# DW1000.net
KiCad netlist of a schematic drawn in Altium Designer
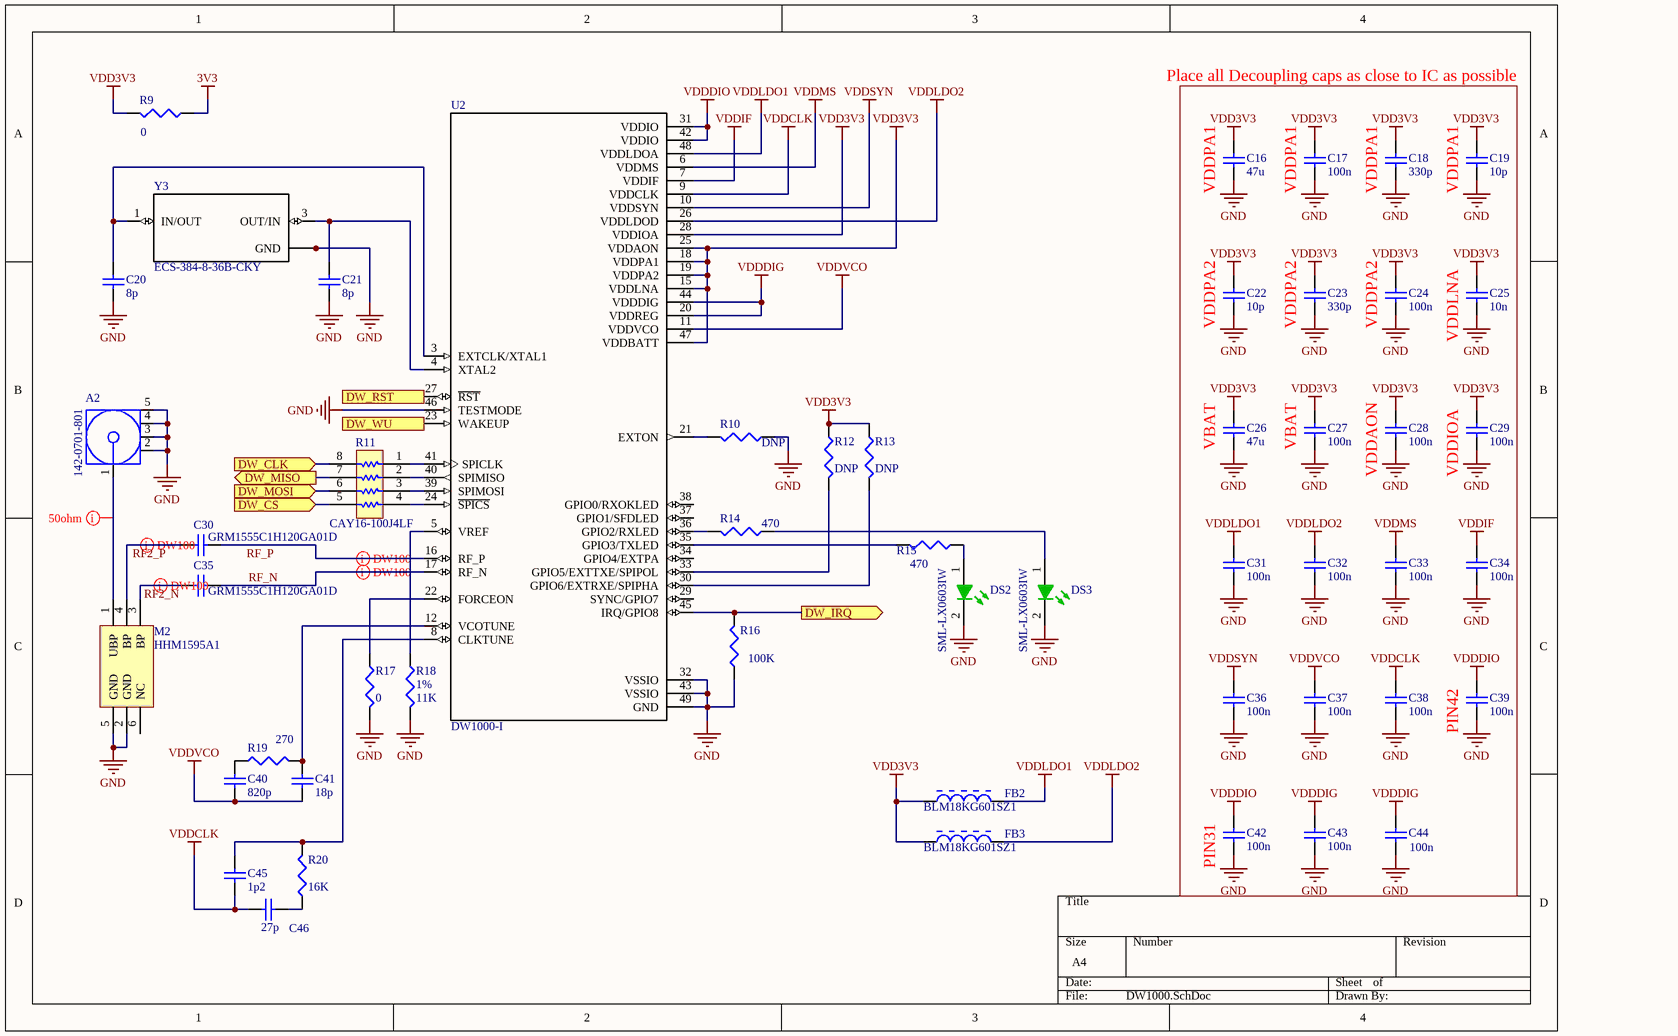
[diagram p0: DW1000.SchDoc]

(export (version "E")
  (design (tool "Eeschema 10.0.6"))
  (components
    (comp (ref "A2")
      (value "142-0701-801")
      (footprint "CINC-142-0701-801_V")
      (description "SMA End Launch Jack Receptacle, 50 Ohm, 0 to 18 GHz, -65 to 165 degC, 5-Pin SMD, RoHS, Bulk")
      (fields (field (name "MANUFACTURER") "EmersonConnectivitySolutions"))
      (libsource (lib "Altium Content Vault") (part "CN-S-4F-RF5"))
    )
    (comp (ref "C16")
      (value "47u")
      (footprint "CAPC1608X90X35NL10T15")
      (fields (field (name "PART NUMBER") "GRM188R71H102KA01D") (field (name "MANUFACTURER") "Murata"))
      (libsource (lib "Altium Content Vault") (part "CAP"))
    )
    (comp (ref "C17")
      (value "100n")
      (footprint "CAPC1608X90X35NL10T15")
      (fields (field (name "PART NUMBER") "GRM188R71H102KA01D") (field (name "MANUFACTURER") "Murata"))
      (libsource (lib "Altium Content Vault") (part "CAP"))
    )
    (comp (ref "C18")
      (value "330p")
      (footprint "CAPC1608X90X35NL10T15")
      (fields (field (name "PART NUMBER") "GRM188R71H102KA01D") (field (name "MANUFACTURER") "Murata"))
      (libsource (lib "Altium Content Vault") (part "CAP"))
    )
    (comp (ref "C19")
      (value "10p")
      (footprint "CAPC1608X90X35NL10T15")
      (fields (field (name "PART NUMBER") "GRM188R71H102KA01D") (field (name "MANUFACTURER") "Murata"))
      (libsource (lib "Altium Content Vault") (part "CAP"))
    )
    (comp (ref "C20")
      (value "8p")
      (footprint "CAPC1608X90X35NL10T15")
      (fields (field (name "PART NUMBER") "GRM188R71H102KA01D") (field (name "MANUFACTURER") "Murata"))
      (libsource (lib "Altium Content Vault") (part "CAP"))
    )
    (comp (ref "C21")
      (value "8p")
      (footprint "CAPC1608X90X35NL10T15")
      (fields (field (name "PART NUMBER") "GRM188R71H102KA01D") (field (name "MANUFACTURER") "Murata"))
      (libsource (lib "Altium Content Vault") (part "CAP"))
    )
    (comp (ref "C22")
      (value "10p")
      (footprint "CAPC1608X90X35NL10T15")
      (fields (field (name "PART NUMBER") "GRM188R71H102KA01D") (field (name "MANUFACTURER") "Murata"))
      (libsource (lib "Altium Content Vault") (part "CAP"))
    )
    (comp (ref "C23")
      (value "330p")
      (footprint "CAPC1608X90X35NL10T15")
      (fields (field (name "PART NUMBER") "GRM188R71H102KA01D") (field (name "MANUFACTURER") "Murata"))
      (libsource (lib "Altium Content Vault") (part "CAP"))
    )
    (comp (ref "C24")
      (value "100n")
      (footprint "CAPC1608X90X35NL10T15")
      (fields (field (name "PART NUMBER") "GRM188R71H102KA01D") (field (name "MANUFACTURER") "Murata"))
      (libsource (lib "Altium Content Vault") (part "CAP"))
    )
    (comp (ref "C25")
      (value "10n")
      (footprint "CAPC1608X90X35NL10T15")
      (fields (field (name "PART NUMBER") "GRM188R71H102KA01D") (field (name "MANUFACTURER") "Murata"))
      (libsource (lib "Altium Content Vault") (part "CAP"))
    )
    (comp (ref "C26")
      (value "47u")
      (footprint "CAPC1608X90X35NL10T15")
      (fields (field (name "PART NUMBER") "GRM188R71H102KA01D") (field (name "MANUFACTURER") "Murata"))
      (libsource (lib "Altium Content Vault") (part "CAP"))
    )
    (comp (ref "C27")
      (value "100n")
      (footprint "CAPC1608X90X35NL10T15")
      (fields (field (name "PART NUMBER") "GRM188R71H102KA01D") (field (name "MANUFACTURER") "Murata"))
      (libsource (lib "Altium Content Vault") (part "CAP"))
    )
    (comp (ref "C28")
      (value "100n")
      (footprint "CAPC1608X90X35NL10T15")
      (fields (field (name "PART NUMBER") "GRM188R71H102KA01D") (field (name "MANUFACTURER") "Murata"))
      (libsource (lib "Altium Content Vault") (part "CAP"))
    )
    (comp (ref "C29")
      (value "100n")
      (footprint "CAPC1608X90X35NL10T15")
      (fields (field (name "PART NUMBER") "GRM188R71H102KA01D") (field (name "MANUFACTURER") "Murata"))
      (libsource (lib "Altium Content Vault") (part "CAP"))
    )
    (comp (ref "C30")
      (value "GRM1555C1H120GA01D")
      (footprint "CAPC1005X55X25ML05T10")
      (fields (field (name "MANUFACTURER") "Murata"))
      (libsource (lib "Altium Content Vault") (part "CAP"))
    )
    (comp (ref "C31")
      (value "100n")
      (footprint "CAPC1608X90X35NL10T15")
      (fields (field (name "PART NUMBER") "GRM188R71H102KA01D") (field (name "MANUFACTURER") "Murata"))
      (libsource (lib "Altium Content Vault") (part "CAP"))
    )
    (comp (ref "C32")
      (value "100n")
      (footprint "CAPC1608X90X35NL10T15")
      (fields (field (name "PART NUMBER") "GRM188R71H102KA01D") (field (name "MANUFACTURER") "Murata"))
      (libsource (lib "Altium Content Vault") (part "CAP"))
    )
    (comp (ref "C33")
      (value "100n")
      (footprint "CAPC1608X90X35NL10T15")
      (fields (field (name "PART NUMBER") "GRM188R71H102KA01D") (field (name "MANUFACTURER") "Murata"))
      (libsource (lib "Altium Content Vault") (part "CAP"))
    )
    (comp (ref "C34")
      (value "100n")
      (footprint "CAPC1608X90X35NL10T15")
      (fields (field (name "PART NUMBER") "GRM188R71H102KA01D") (field (name "MANUFACTURER") "Murata"))
      (libsource (lib "Altium Content Vault") (part "CAP"))
    )
    (comp (ref "C35")
      (value "GRM1555C1H120GA01D")
      (footprint "CAPC1005X55X25ML05T10")
      (fields (field (name "MANUFACTURER") "Murata"))
      (libsource (lib "Altium Content Vault") (part "CAP"))
    )
    (comp (ref "C36")
      (value "100n")
      (footprint "CAPC1608X90X35NL10T15")
      (fields (field (name "PART NUMBER") "GRM188R71H102KA01D") (field (name "MANUFACTURER") "Murata"))
      (libsource (lib "Altium Content Vault") (part "CAP"))
    )
    (comp (ref "C37")
      (value "100n")
      (footprint "CAPC1608X90X35NL10T15")
      (fields (field (name "PART NUMBER") "GRM188R71H102KA01D") (field (name "MANUFACTURER") "Murata"))
      (libsource (lib "Altium Content Vault") (part "CAP"))
    )
    (comp (ref "C38")
      (value "100n")
      (footprint "CAPC1608X90X35NL10T15")
      (fields (field (name "PART NUMBER") "GRM188R71H102KA01D") (field (name "MANUFACTURER") "Murata"))
      (libsource (lib "Altium Content Vault") (part "CAP"))
    )
    (comp (ref "C39")
      (value "100n")
      (footprint "CAPC1608X90X35NL10T15")
      (fields (field (name "PART NUMBER") "GRM188R71H102KA01D") (field (name "MANUFACTURER") "Murata"))
      (libsource (lib "Altium Content Vault") (part "CAP"))
    )
    (comp (ref "C40")
      (value "820p")
      (footprint "CAPC1608X90X35NL10T15")
      (fields (field (name "PART NUMBER") "GRM188R71H102KA01D") (field (name "MANUFACTURER") "Murata"))
      (libsource (lib "Altium Content Vault") (part "CAP"))
    )
    (comp (ref "C41")
      (value "18p")
      (footprint "CAPC1608X90X35NL10T15")
      (fields (field (name "PART NUMBER") "GRM188R71H102KA01D") (field (name "MANUFACTURER") "Murata"))
      (libsource (lib "Altium Content Vault") (part "CAP"))
    )
    (comp (ref "C42")
      (value "100n")
      (footprint "CAPC1608X90X35NL10T15")
      (fields (field (name "PART NUMBER") "GRM188R71H102KA01D") (field (name "MANUFACTURER") "Murata"))
      (libsource (lib "Altium Content Vault") (part "CAP"))
    )
    (comp (ref "C43")
      (value "100n")
      (footprint "CAPC1608X90X35NL10T15")
      (fields (field (name "PART NUMBER") "GRM188R71H102KA01D") (field (name "MANUFACTURER") "Murata"))
      (libsource (lib "Altium Content Vault") (part "CAP"))
    )
    (comp (ref "C44")
      (value "100n")
      (footprint "CAPC1608X90X35NL10T15")
      (fields (field (name "PART NUMBER") "GRM188R71H102KA01D") (field (name "MANUFACTURER") "Murata"))
      (libsource (lib "Altium Content Vault") (part "CAP"))
    )
    (comp (ref "C45")
      (value "1p2")
      (footprint "CAPC1608X90X35NL10T15")
      (fields (field (name "PART NUMBER") "GRM188R71H102KA01D") (field (name "MANUFACTURER") "Murata"))
      (libsource (lib "Altium Content Vault") (part "CAP"))
    )
    (comp (ref "C46")
      (value "27p")
      (footprint "CAPC1608X90X35NL10T15")
      (fields (field (name "PART NUMBER") "GRM188R71H102KA01D") (field (name "MANUFACTURER") "Murata"))
      (libsource (lib "Altium Content Vault") (part "CAP"))
    )
    (comp (ref "DS2")
      (value "SML-LX0603IW")
      (footprint "KING-0603LED_GREEN_V")
      (description "LED, SMT, 0603(1608), 1.1mm thickness, Green")
      (fields (field (name "MANUFACTURER") "Kingbright") (field (name "PARTNUMBER") "KP-1608MGC"))
      (libsource (lib "Altium Content Vault") (part "KING-LED-GREEN-A1K2-2"))
    )
    (comp (ref "DS3")
      (value "SML-LX0603IW")
      (footprint "KING-0603LED_GREEN_V")
      (description "LED, SMT, 0603(1608), 1.1mm thickness, Green")
      (fields (field (name "MANUFACTURER") "Kingbright") (field (name "PARTNUMBER") "KP-1608MGC"))
      (libsource (lib "Altium Content Vault") (part "KING-LED-GREEN-A1K2-2"))
    )
    (comp (ref "FB2")
      (value "BLM18KG601SZ1")
      (footprint "MURA-BLM18SG-B25-CHIP-2_V1")
      (fields (field (name "MANUFACTURER") "Murata") (field (name "PARTNUMBER") "BLM18SG221TN1D"))
      (libsource (lib "Altium Content Vault") (part "MURA-FB-2"))
    )
    (comp (ref "FB3")
      (value "BLM18KG601SZ1")
      (footprint "MURA-BLM18SG-B25-CHIP-2_V1")
      (fields (field (name "MANUFACTURER") "Murata") (field (name "PARTNUMBER") "BLM18SG221TN1D"))
      (libsource (lib "Altium Content Vault") (part "MURA-FB-2"))
    )
    (comp (ref "M2")
      (value "HHM1595A1")
      (footprint "TDK-HHM1595A1_V")
      (description "Multilayer Balun, 3000 to 8000 MHz, -40 to 85 degC, 6-Pin SMD, RoHS, Tape and Reel")
      (fields (field (name "MANUFACTURER") "TDK"))
      (libsource (lib "Altium Content Vault") (part "TDK-HHM1595A1-6"))
    )
    (comp (ref "R9")
      (value "0")
      (footprint "J1-0603")
      (description "Resistor")
      (fields (field (name "PUBLISHER") "Altium Limited"))
      (libsource (lib "Miscellaneous Devices") (part "Res3"))
    )
    (comp (ref "R10")
      (value "DNP")
      (footprint "J1-0603")
      (description "Resistor")
      (fields (field (name "PUBLISHER") "Altium Limited"))
      (libsource (lib "Miscellaneous Devices") (part "Res3"))
    )
    (comp (ref "R11")
      (value "CAY16-100J4LF")
      (footprint "BOUR-CAY16-J4_V")
      (description "Chip Resistor Array, 1 KOhm, +/- 5%, 62.5 mW, -55 to 125 degC, 8-Pin SMD, RoHS, Tape and Reel")
      (fields (field (name "TOLERANCE") "1%"))
      (libsource (lib "Altium Content Vault") (part "RES-P-8"))
    )
    (comp (ref "R12")
      (value "DNP")
      (footprint "J1-0603")
      (description "Resistor")
      (fields (field (name "PUBLISHER") "Altium Limited"))
      (libsource (lib "Miscellaneous Devices") (part "Res3"))
    )
    (comp (ref "R13")
      (value "DNP")
      (footprint "J1-0603")
      (description "Resistor")
      (fields (field (name "PUBLISHER") "Altium Limited"))
      (libsource (lib "Miscellaneous Devices") (part "Res3"))
    )
    (comp (ref "R14")
      (value "470")
      (footprint "J1-0603")
      (description "Resistor")
      (fields (field (name "PUBLISHER") "Altium Limited"))
      (libsource (lib "Miscellaneous Devices") (part "Res3"))
    )
    (comp (ref "R15")
      (value "470")
      (footprint "J1-0603")
      (description "Resistor")
      (fields (field (name "PUBLISHER") "Altium Limited"))
      (libsource (lib "Miscellaneous Devices") (part "Res3"))
    )
    (comp (ref "R16")
      (value "100K")
      (footprint "J1-0603")
      (description "Resistor")
      (fields (field (name "PUBLISHER") "Altium Limited"))
      (libsource (lib "Miscellaneous Devices") (part "Res3"))
    )
    (comp (ref "R17")
      (value "0")
      (footprint "J1-0603")
      (description "Resistor")
      (fields (field (name "PUBLISHER") "Altium Limited"))
      (libsource (lib "Miscellaneous Devices") (part "Res3"))
    )
    (comp (ref "R18")
      (value "1%")
      (footprint "J1-0603")
      (description "Resistor")
      (fields (field (name "ALTIUM_VALUE") "11K") (field (name "PUBLISHER") "Altium Limited"))
      (libsource (lib "Miscellaneous Devices") (part "Res3"))
    )
    (comp (ref "R19")
      (value "270")
      (footprint "J1-0603")
      (description "Resistor")
      (fields (field (name "PUBLISHER") "Altium Limited"))
      (libsource (lib "Miscellaneous Devices") (part "Res3"))
    )
    (comp (ref "R20")
      (value "16K")
      (footprint "J1-0603")
      (description "Resistor")
      (fields (field (name "PUBLISHER") "Altium Limited"))
      (libsource (lib "Miscellaneous Devices") (part "Res3"))
    )
    (comp (ref "U2")
      (value "DW1000-I")
      (footprint "*QFN40P600X600X90-49N")
      (description "Ic Rf Txrx 802.15.4 48-Qfn")
      (fields (field (name "MF") "Decawave Limited"))
      (libsource (lib "DW1000-I") (part "DW1000-I"))
    )
    (comp (ref "Y3")
      (value "ECS-384-8-36B-CKY")
      (footprint "*XTAL_ECS-240-8-36-CKM-TR")
      (fields (field (name "MF") "ECS Inc.") (field (name "MP") "ECS-240-8-36-CKM-TR"))
      (libsource (lib "ECS-240-8-36-CKM-TR") (part "ECS-240-8-36-CKM-TR"))
    )
  )
  (nets
    (net (code "1") (name "/DW_CLK") (class "Default")
      (node (ref "R11") (pin "8") (pinfunction "8_8") (pintype "passive"))
    )
    (net (code "2") (name "/DW_CS") (class "Default")
      (node (ref "R11") (pin "5") (pinfunction "5_5") (pintype "passive"))
    )
    (net (code "3") (name "/DW_IRQ") (class "Default")
      (node (ref "R16") (pin "2") (pinfunction "2_2") (pintype "passive"))
      (node (ref "U2") (pin "45") (pinfunction "IRQ/GPIO8_45") (pintype "bidirectional"))
    )
    (net (code "4") (name "/DW_MISO") (class "Default")
      (node (ref "R11") (pin "7") (pinfunction "7_7") (pintype "passive"))
    )
    (net (code "5") (name "/DW_MOSI") (class "Default")
      (node (ref "R11") (pin "6") (pinfunction "6_6") (pintype "passive"))
    )
    (net (code "6") (name "/DW_RST") (class "Default")
      (node (ref "U2") (pin "27") (pinfunction "~{RST}_27") (pintype "bidirectional"))
    )
    (net (code "7") (name "/DW_WU") (class "Default")
      (node (ref "U2") (pin "23") (pinfunction "WAKEUP_23") (pintype "input"))
    )
    (net (code "8") (name "/RF2_N") (class "Default")
      (node (ref "C35") (pin "1") (pinfunction "1_1") (pintype "passive"))
      (node (ref "M2") (pin "3") (pinfunction "BP_3") (pintype "passive"))
    )
    (net (code "9") (name "/RF2_P") (class "Default")
      (node (ref "C30") (pin "1") (pinfunction "1_1") (pintype "passive"))
      (node (ref "M2") (pin "4") (pinfunction "BP_4") (pintype "passive"))
    )
    (net (code "10") (name "/RF_N") (class "Default")
      (node (ref "C35") (pin "2") (pinfunction "2_2") (pintype "passive"))
      (node (ref "U2") (pin "17") (pinfunction "RF_N_17") (pintype "bidirectional"))
    )
    (net (code "11") (name "/RF_P") (class "Default")
      (node (ref "C30") (pin "2") (pinfunction "2_2") (pintype "passive"))
      (node (ref "U2") (pin "16") (pinfunction "RF_P_16") (pintype "bidirectional"))
    )
    (net (code "12") (name "3V3") (class "Default")
      (node (ref "R9") (pin "1") (pinfunction "1_1") (pintype "passive"))
    )
    (net (code "13") (name "GND") (class "Default")
      (node (ref "A2") (pin "2") (pinfunction "2_2") (pintype "passive"))
      (node (ref "A2") (pin "3") (pinfunction "3_3") (pintype "passive"))
      (node (ref "A2") (pin "4") (pinfunction "4_4") (pintype "passive"))
      (node (ref "A2") (pin "5") (pinfunction "5_5") (pintype "passive"))
      (node (ref "C16") (pin "1") (pinfunction "1_1") (pintype "passive"))
      (node (ref "C17") (pin "1") (pinfunction "1_1") (pintype "passive"))
      (node (ref "C18") (pin "1") (pinfunction "1_1") (pintype "passive"))
      (node (ref "C19") (pin "1") (pinfunction "1_1") (pintype "passive"))
      (node (ref "C20") (pin "1") (pinfunction "1_1") (pintype "passive"))
      (node (ref "C21") (pin "1") (pinfunction "1_1") (pintype "passive"))
      (node (ref "C22") (pin "1") (pinfunction "1_1") (pintype "passive"))
      (node (ref "C23") (pin "1") (pinfunction "1_1") (pintype "passive"))
      (node (ref "C24") (pin "1") (pinfunction "1_1") (pintype "passive"))
      (node (ref "C25") (pin "1") (pinfunction "1_1") (pintype "passive"))
      (node (ref "C26") (pin "1") (pinfunction "1_1") (pintype "passive"))
      (node (ref "C27") (pin "1") (pinfunction "1_1") (pintype "passive"))
      (node (ref "C28") (pin "1") (pinfunction "1_1") (pintype "passive"))
      (node (ref "C29") (pin "1") (pinfunction "1_1") (pintype "passive"))
      (node (ref "C31") (pin "1") (pinfunction "1_1") (pintype "passive"))
      (node (ref "C32") (pin "1") (pinfunction "1_1") (pintype "passive"))
      (node (ref "C33") (pin "1") (pinfunction "1_1") (pintype "passive"))
      (node (ref "C34") (pin "1") (pinfunction "1_1") (pintype "passive"))
      (node (ref "C36") (pin "1") (pinfunction "1_1") (pintype "passive"))
      (node (ref "C37") (pin "1") (pinfunction "1_1") (pintype "passive"))
      (node (ref "C38") (pin "1") (pinfunction "1_1") (pintype "passive"))
      (node (ref "C39") (pin "1") (pinfunction "1_1") (pintype "passive"))
      (node (ref "C42") (pin "1") (pinfunction "1_1") (pintype "passive"))
      (node (ref "C43") (pin "1") (pinfunction "1_1") (pintype "passive"))
      (node (ref "C44") (pin "1") (pinfunction "1_1") (pintype "passive"))
      (node (ref "DS2") (pin "2") (pinfunction "K_2") (pintype "passive"))
      (node (ref "DS3") (pin "2") (pinfunction "K_2") (pintype "passive"))
      (node (ref "M2") (pin "2") (pinfunction "GND_2") (pintype "power_in"))
      (node (ref "M2") (pin "5") (pinfunction "GND_5") (pintype "power_in"))
      (node (ref "R10") (pin "1") (pinfunction "1_1") (pintype "passive"))
      (node (ref "R16") (pin "1") (pinfunction "1_1") (pintype "passive"))
      (node (ref "R17") (pin "2") (pinfunction "2_2") (pintype "passive"))
      (node (ref "R18") (pin "2") (pinfunction "2_2") (pintype "passive"))
      (node (ref "U2") (pin "32") (pinfunction "VSSIO_32") (pintype "power_in"))
      (node (ref "U2") (pin "43") (pinfunction "VSSIO_43") (pintype "power_in"))
      (node (ref "U2") (pin "46") (pinfunction "TESTMODE_46") (pintype "input"))
      (node (ref "U2") (pin "49") (pinfunction "GND_49") (pintype "power_in"))
      (node (ref "Y3") (pin "2") (pinfunction "GND_2") (pintype "power_in"))
      (node (ref "Y3") (pin "4") (pinfunction "GND_4") (pintype "power_in"))
    )
    (net (code "14") (name "Net-(C40-Pad2)") (class "Default")
      (node (ref "C40") (pin "2") (pinfunction "2_2") (pintype "passive"))
      (node (ref "R19") (pin "1") (pinfunction "1_1") (pintype "passive"))
    )
    (net (code "15") (name "Net-(C46-Pad1)") (class "Default")
      (node (ref "C46") (pin "1") (pinfunction "1_1") (pintype "passive"))
      (node (ref "R20") (pin "1") (pinfunction "1_1") (pintype "passive"))
    )
    (net (code "16") (name "Net-(DS2-A)") (class "Default")
      (node (ref "DS2") (pin "1") (pinfunction "A_1") (pintype "passive"))
      (node (ref "R15") (pin "1") (pinfunction "1_1") (pintype "passive"))
    )
    (net (code "17") (name "Net-(DS3-A)") (class "Default")
      (node (ref "DS3") (pin "1") (pinfunction "A_1") (pintype "passive"))
      (node (ref "R14") (pin "1") (pinfunction "1_1") (pintype "passive"))
    )
    (net (code "18") (name "Net-(M2-UBP)") (class "Default")
      (node (ref "A2") (pin "1") (pinfunction "1_1") (pintype "passive"))
      (node (ref "M2") (pin "1") (pinfunction "UBP_1") (pintype "passive"))
    )
    (net (code "19") (name "Net-(U2-CLKTUNE)") (class "Default")
      (node (ref "C45") (pin "2") (pinfunction "2_2") (pintype "passive"))
      (node (ref "R20") (pin "2") (pinfunction "2_2") (pintype "passive"))
      (node (ref "U2") (pin "8") (pinfunction "CLKTUNE_8") (pintype "bidirectional"))
    )
    (net (code "20") (name "Net-(U2-EXTCLK{slash}XTAL1)") (class "Default")
      (node (ref "C20") (pin "2") (pinfunction "2_2") (pintype "passive"))
      (node (ref "U2") (pin "3") (pinfunction "EXTCLK/XTAL1_3") (pintype "input"))
      (node (ref "Y3") (pin "1") (pinfunction "IN/OUT_1") (pintype "bidirectional"))
    )
    (net (code "21") (name "Net-(U2-EXTON)") (class "Default")
      (node (ref "R10") (pin "2") (pinfunction "2_2") (pintype "passive"))
      (node (ref "U2") (pin "21") (pinfunction "EXTON_21") (pintype "output"))
    )
    (net (code "22") (name "Net-(U2-FORCEON)") (class "Default")
      (node (ref "R17") (pin "1") (pinfunction "1_1") (pintype "passive"))
      (node (ref "U2") (pin "22") (pinfunction "FORCEON_22") (pintype "bidirectional"))
    )
    (net (code "23") (name "Net-(U2-GPIO2{slash}RXLED)") (class "Default")
      (node (ref "R14") (pin "2") (pinfunction "2_2") (pintype "passive"))
      (node (ref "U2") (pin "36") (pinfunction "GPIO2/RXLED_36") (pintype "bidirectional"))
    )
    (net (code "24") (name "Net-(U2-GPIO3{slash}TXLED)") (class "Default")
      (node (ref "R15") (pin "2") (pinfunction "2_2") (pintype "passive"))
      (node (ref "U2") (pin "35") (pinfunction "GPIO3/TXLED_35") (pintype "bidirectional"))
    )
    (net (code "25") (name "Net-(U2-GPIO5{slash}EXTTXE{slash}SPIPOL)") (class "Default")
      (node (ref "R12") (pin "2") (pinfunction "2_2") (pintype "passive"))
      (node (ref "U2") (pin "33") (pinfunction "GPIO5/EXTTXE/SPIPOL_33") (pintype "bidirectional"))
    )
    (net (code "26") (name "Net-(U2-GPIO6{slash}EXTRXE{slash}SPIPHA)") (class "Default")
      (node (ref "R13") (pin "2") (pinfunction "2_2") (pintype "passive"))
      (node (ref "U2") (pin "30") (pinfunction "GPIO6/EXTRXE/SPIPHA_30") (pintype "bidirectional"))
    )
    (net (code "27") (name "Net-(U2-SPICLK)") (class "Default")
      (node (ref "R11") (pin "1") (pinfunction "1_1") (pintype "passive"))
      (node (ref "U2") (pin "41") (pinfunction "SPICLK_41") (pintype "input"))
    )
    (net (code "28") (name "Net-(U2-SPIMISO)") (class "Default")
      (node (ref "R11") (pin "2") (pinfunction "2_2") (pintype "passive"))
      (node (ref "U2") (pin "40") (pinfunction "SPIMISO_40") (pintype "output"))
    )
    (net (code "29") (name "Net-(U2-SPIMOSI)") (class "Default")
      (node (ref "R11") (pin "3") (pinfunction "3_3") (pintype "passive"))
      (node (ref "U2") (pin "39") (pinfunction "SPIMOSI_39") (pintype "input"))
    )
    (net (code "30") (name "Net-(U2-VCOTUNE)") (class "Default")
      (node (ref "C41") (pin "2") (pinfunction "2_2") (pintype "passive"))
      (node (ref "R19") (pin "2") (pinfunction "2_2") (pintype "passive"))
      (node (ref "U2") (pin "12") (pinfunction "VCOTUNE_12") (pintype "bidirectional"))
    )
    (net (code "31") (name "Net-(U2-VREF)") (class "Default")
      (node (ref "R18") (pin "1") (pinfunction "1_1") (pintype "passive"))
      (node (ref "U2") (pin "5") (pinfunction "VREF_5") (pintype "bidirectional"))
    )
    (net (code "32") (name "Net-(U2-XTAL2)") (class "Default")
      (node (ref "C21") (pin "2") (pinfunction "2_2") (pintype "passive"))
      (node (ref "U2") (pin "4") (pinfunction "XTAL2_4") (pintype "input"))
      (node (ref "Y3") (pin "3") (pinfunction "OUT/IN_3") (pintype "bidirectional"))
    )
    (net (code "33") (name "Net-(U2-~{SPICS})") (class "Default")
      (node (ref "R11") (pin "4") (pinfunction "4_4") (pintype "passive"))
      (node (ref "U2") (pin "24") (pinfunction "~{SPICS}_24") (pintype "input"))
    )
    (net (code "34") (name "VDD3V3") (class "Default")
      (node (ref "C16") (pin "2") (pinfunction "2_2") (pintype "passive"))
      (node (ref "C17") (pin "2") (pinfunction "2_2") (pintype "passive"))
      (node (ref "C18") (pin "2") (pinfunction "2_2") (pintype "passive"))
      (node (ref "C19") (pin "2") (pinfunction "2_2") (pintype "passive"))
      (node (ref "C22") (pin "2") (pinfunction "2_2") (pintype "passive"))
      (node (ref "C23") (pin "2") (pinfunction "2_2") (pintype "passive"))
      (node (ref "C24") (pin "2") (pinfunction "2_2") (pintype "passive"))
      (node (ref "C25") (pin "2") (pinfunction "2_2") (pintype "passive"))
      (node (ref "C26") (pin "2") (pinfunction "2_2") (pintype "passive"))
      (node (ref "C27") (pin "2") (pinfunction "2_2") (pintype "passive"))
      (node (ref "C28") (pin "2") (pinfunction "2_2") (pintype "passive"))
      (node (ref "C29") (pin "2") (pinfunction "2_2") (pintype "passive"))
      (node (ref "FB2") (pin "1") (pinfunction "1_1") (pintype "passive"))
      (node (ref "FB3") (pin "1") (pinfunction "1_1") (pintype "passive"))
      (node (ref "R12") (pin "1") (pinfunction "1_1") (pintype "passive"))
      (node (ref "R13") (pin "1") (pinfunction "1_1") (pintype "passive"))
      (node (ref "R9") (pin "2") (pinfunction "2_2") (pintype "passive"))
      (node (ref "U2") (pin "15") (pinfunction "VDDLNA_15") (pintype "power_in"))
      (node (ref "U2") (pin "18") (pinfunction "VDDPA1_18") (pintype "power_in"))
      (node (ref "U2") (pin "19") (pinfunction "VDDPA2_19") (pintype "power_in"))
      (node (ref "U2") (pin "25") (pinfunction "VDDAON_25") (pintype "power_in"))
      (node (ref "U2") (pin "28") (pinfunction "VDDIOA_28") (pintype "power_in"))
      (node (ref "U2") (pin "47") (pinfunction "VDDBATT_47") (pintype "power_in"))
    )
    (net (code "35") (name "VDDCLK") (class "Default")
      (node (ref "C38") (pin "2") (pinfunction "2_2") (pintype "passive"))
      (node (ref "C45") (pin "1") (pinfunction "1_1") (pintype "passive"))
      (node (ref "C46") (pin "2") (pinfunction "2_2") (pintype "passive"))
      (node (ref "U2") (pin "9") (pinfunction "VDDCLK_9") (pintype "power_in"))
    )
    (net (code "36") (name "VDDDIG") (class "Default")
      (node (ref "C43") (pin "2") (pinfunction "2_2") (pintype "passive"))
      (node (ref "C44") (pin "2") (pinfunction "2_2") (pintype "passive"))
      (node (ref "U2") (pin "20") (pinfunction "VDDREG_20") (pintype "power_in"))
      (node (ref "U2") (pin "44") (pinfunction "VDDDIG_44") (pintype "power_in"))
    )
    (net (code "37") (name "VDDDIO") (class "Default")
      (node (ref "C39") (pin "2") (pinfunction "2_2") (pintype "passive"))
      (node (ref "C42") (pin "2") (pinfunction "2_2") (pintype "passive"))
      (node (ref "U2") (pin "31") (pinfunction "VDDIO_31") (pintype "power_in"))
      (node (ref "U2") (pin "42") (pinfunction "VDDIO_42") (pintype "power_in"))
    )
    (net (code "38") (name "VDDIF") (class "Default")
      (node (ref "C34") (pin "2") (pinfunction "2_2") (pintype "passive"))
      (node (ref "U2") (pin "7") (pinfunction "VDDIF_7") (pintype "power_in"))
    )
    (net (code "39") (name "VDDLDO1") (class "Default")
      (node (ref "C31") (pin "2") (pinfunction "2_2") (pintype "passive"))
      (node (ref "FB2") (pin "2") (pinfunction "2_2") (pintype "passive"))
      (node (ref "U2") (pin "48") (pinfunction "VDDLDOA_48") (pintype "power_in"))
    )
    (net (code "40") (name "VDDLDO2") (class "Default")
      (node (ref "C32") (pin "2") (pinfunction "2_2") (pintype "passive"))
      (node (ref "FB3") (pin "2") (pinfunction "2_2") (pintype "passive"))
      (node (ref "U2") (pin "26") (pinfunction "VDDLDOD_26") (pintype "power_in"))
    )
    (net (code "41") (name "VDDMS") (class "Default")
      (node (ref "C33") (pin "2") (pinfunction "2_2") (pintype "passive"))
      (node (ref "U2") (pin "6") (pinfunction "VDDMS_6") (pintype "power_in"))
    )
    (net (code "42") (name "VDDSYN") (class "Default")
      (node (ref "C36") (pin "2") (pinfunction "2_2") (pintype "passive"))
      (node (ref "U2") (pin "10") (pinfunction "VDDSYN_10") (pintype "power_in"))
    )
    (net (code "43") (name "VDDVCO") (class "Default")
      (node (ref "C37") (pin "2") (pinfunction "2_2") (pintype "passive"))
      (node (ref "C40") (pin "1") (pinfunction "1_1") (pintype "passive"))
      (node (ref "C41") (pin "1") (pinfunction "1_1") (pintype "passive"))
      (node (ref "U2") (pin "11") (pinfunction "VDDVCO_11") (pintype "power_in"))
    )
    (net (code "44") (name "unconnected-(M2-NC-Pad6)") (class "Default")
      (node (ref "M2") (pin "6") (pinfunction "NC_6") (pintype "passive"))
    )
    (net (code "45") (name "unconnected-(U2-GPIO0{slash}RXOKLED-Pad38)") (class "Default")
      (node (ref "U2") (pin "38") (pinfunction "GPIO0/RXOKLED_38") (pintype "bidirectional"))
    )
    (net (code "46") (name "unconnected-(U2-GPIO1{slash}SFDLED-Pad37)") (class "Default")
      (node (ref "U2") (pin "37") (pinfunction "GPIO1/SFDLED_37") (pintype "bidirectional"))
    )
    (net (code "47") (name "unconnected-(U2-GPIO4{slash}EXTPA-Pad34)") (class "Default")
      (node (ref "U2") (pin "34") (pinfunction "GPIO4/EXTPA_34") (pintype "bidirectional"))
    )
    (net (code "48") (name "unconnected-(U2-SYNC{slash}GPIO7-Pad29)") (class "Default")
      (node (ref "U2") (pin "29") (pinfunction "SYNC/GPIO7_29") (pintype "bidirectional"))
    )
  )
)
